# PM12_ADT7311.net
KiCad netlist of a schematic drawn in Altium Designer
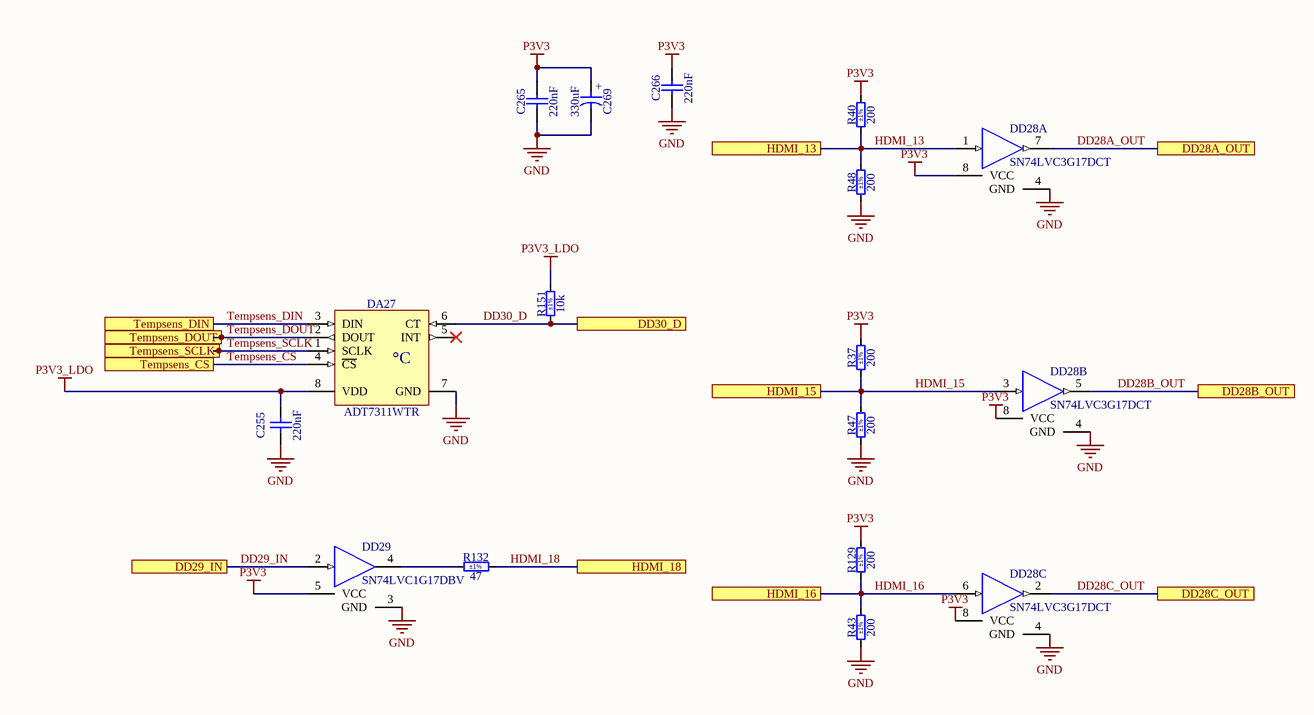
[diagram p0: PM12_ADT7311.SchDoc]

(export (version "E")
  (design (tool "Eeschema 10.0.6"))
  (components
    (comp (ref "C255")
      (value "220nF")
      (footprint "CAPC2012X135N")
      (description "Non-polarised capacitor")
      (fields
        (field (name "PART NUMBER") "CC0805_220NF_50V_10%_X7R")
        (field (name "VOLTAGE") "50V")
        (field (name "AUTHOR") "CERN DEM JLC")
      )
      (libsource (lib "Capacitors") (part "Capacitor - non polarized"))
    )
    (comp (ref "C265")
      (value "220nF")
      (footprint "CAPC2012X135N")
      (description "Non-polarised capacitor")
      (fields
        (field (name "PART NUMBER") "CC0805_220NF_50V_10%_X7R")
        (field (name "VOLTAGE") "50V")
        (field (name "AUTHOR") "CERN DEM JLC")
      )
      (libsource (lib "Capacitors") (part "Capacitor - non polarized"))
    )
    (comp (ref "C266")
      (value "220nF")
      (footprint "CAPC2012X135N")
      (description "Non-polarised capacitor")
      (fields
        (field (name "PART NUMBER") "CC0805_220NF_50V_10%_X7R")
        (field (name "VOLTAGE") "50V")
        (field (name "AUTHOR") "CERN DEM JLC")
      )
      (libsource (lib "Capacitors") (part "Capacitor - non polarized"))
    )
    (comp (ref "C269")
      (value "330uF")
      (footprint "CAPMP7343X310N")
      (description "Polarised capacitor")
      (fields
        (field (name "PART NUMBER") "CTE7343-31_330UF_6.3V_20%_LESR0015_KEMET_T520")
        (field (name "VOLTAGE") "6.3V")
        (field (name "AUTHOR") "CERN DEM JLC")
      )
      (libsource (lib "Capacitors") (part "Capacitor - polarized"))
    )
    (comp (ref "DA27")
      (value "ADT7311WTR")
      (footprint "SOIC127P600X175-8N")
      (description "±0.5°C Accurate, 16-Bit Digital SPI Temperature Sensor")
      (fields (field (name "MANUFACTURER") "ANALOG DEVICES") (field (name "AUTHOR") "CERN DEM HF"))
      (libsource (lib "ICs And Semiconductors") (part "ADT7311WTR"))
    )
    (comp (ref "DD28")
      (value "SN74LVC3G17DCT")
      (footprint "SOP65P400X130-8N")
      (description "Triple Schmitt-Trigger Buffer")
      (fields (field (name "MANUFACTURER") "TEXAS INSTRUMENTS") (field (name "AUTHOR") "CERN DEM HF"))
      (libsource (lib "ICs And Semiconductors") (part "743G17"))
    )
    (comp (ref "DD29")
      (value "SN74LVC1G17DBV")
      (footprint "SOT95P280X145-5N")
      (description "Single Schmitt-Trigger Buffer")
      (fields
        (field (name "PART NUMBER") "SN74LVC1G17DBVR")
        (field (name "MANUFACTURER") "TEXAS INSTRUMENTS")
        (field (name "AUTHOR") "CERN DEM JLC")
      )
      (libsource (lib "ICs And Semiconductors") (part "741G17"))
    )
    (comp (ref "R37")
      (value "200")
      (footprint "RESC2012X60N")
      (description "Resistor - 1%")
      (fields
        (field (name "TOLERANCE") "±1%")
        (field (name "PART NUMBER") "R0805_200R_1%_0.125W_100PPM")
        (field (name "POWER") "0.125W")
        (field (name "AUTHOR") "CERN DEM JLC")
      )
      (libsource (lib "Resistors") (part "Resistor - 1%"))
    )
    (comp (ref "R40")
      (value "200")
      (footprint "RESC2012X60N")
      (description "Resistor - 1%")
      (fields
        (field (name "TOLERANCE") "±1%")
        (field (name "PART NUMBER") "R0805_200R_1%_0.125W_100PPM")
        (field (name "POWER") "0.125W")
        (field (name "AUTHOR") "CERN DEM JLC")
      )
      (libsource (lib "Resistors") (part "Resistor - 1%"))
    )
    (comp (ref "R43")
      (value "200")
      (footprint "RESC2012X60N")
      (description "Resistor - 1%")
      (fields
        (field (name "TOLERANCE") "±1%")
        (field (name "PART NUMBER") "R0805_200R_1%_0.125W_100PPM")
        (field (name "POWER") "0.125W")
        (field (name "AUTHOR") "CERN DEM JLC")
      )
      (libsource (lib "Resistors") (part "Resistor - 1%"))
    )
    (comp (ref "R47")
      (value "200")
      (footprint "RESC2012X60N")
      (description "Resistor - 1%")
      (fields
        (field (name "TOLERANCE") "±1%")
        (field (name "PART NUMBER") "R0805_200R_1%_0.125W_100PPM")
        (field (name "POWER") "0.125W")
        (field (name "AUTHOR") "CERN DEM JLC")
      )
      (libsource (lib "Resistors") (part "Resistor - 1%"))
    )
    (comp (ref "R48")
      (value "200")
      (footprint "RESC2012X60N")
      (description "Resistor - 1%")
      (fields
        (field (name "TOLERANCE") "±1%")
        (field (name "PART NUMBER") "R0805_200R_1%_0.125W_100PPM")
        (field (name "POWER") "0.125W")
        (field (name "AUTHOR") "CERN DEM JLC")
      )
      (libsource (lib "Resistors") (part "Resistor - 1%"))
    )
    (comp (ref "R129")
      (value "200")
      (footprint "RESC2012X60N")
      (description "Resistor - 1%")
      (fields
        (field (name "TOLERANCE") "±1%")
        (field (name "PART NUMBER") "R0805_200R_1%_0.125W_100PPM")
        (field (name "POWER") "0.125W")
        (field (name "AUTHOR") "CERN DEM JLC")
      )
      (libsource (lib "Resistors") (part "Resistor - 1%"))
    )
    (comp (ref "R132")
      (value "47")
      (footprint "RESC2012X60N")
      (description "Resistor - 1%")
      (fields
        (field (name "TOLERANCE") "±1%")
        (field (name "PART NUMBER") "R0805_47R_1%_0.125W_100PPM")
        (field (name "POWER") "0.125W")
        (field (name "AUTHOR") "CERN DEM JLC")
      )
      (libsource (lib "Resistors") (part "Resistor - 1%"))
    )
    (comp (ref "R151")
      (value "10k")
      (footprint "RESC2012X60N")
      (description "Resistor - 1%")
      (fields
        (field (name "TOLERANCE") "±1%")
        (field (name "PART NUMBER") "R0805_10K_1%_0.125W_100PPM")
        (field (name "POWER") "0.125W")
        (field (name "AUTHOR") "CERN DEM JLC")
      )
      (libsource (lib "Resistors") (part "Resistor - 1%"))
    )
  )
  (nets
    (net (code "1") (name "/DD28A_OUT") (class "Default")
      (node (ref "DD28") (pin "7") (pinfunction "OUT_7") (pintype "output"))
    )
    (net (code "2") (name "/DD28B_OUT") (class "Default")
      (node (ref "DD28") (pin "5") (pinfunction "OUT_5") (pintype "output"))
    )
    (net (code "3") (name "/DD28C_OUT") (class "Default")
      (node (ref "DD28") (pin "2") (pinfunction "OUT_2") (pintype "output"))
    )
    (net (code "4") (name "/DD29_IN") (class "Default")
      (node (ref "DD29") (pin "2") (pinfunction "IN_2") (pintype "input"))
    )
    (net (code "5") (name "/DD30_D") (class "Default")
      (node (ref "DA27") (pin "6") (pinfunction "CT_6") (pintype "input"))
      (node (ref "R151") (pin "1") (pinfunction "1_1") (pintype "passive"))
    )
    (net (code "6") (name "/HDMI_13") (class "Default")
      (node (ref "DD28") (pin "1") (pinfunction "IN_1") (pintype "input"))
      (node (ref "R40") (pin "1") (pinfunction "1_1") (pintype "passive"))
      (node (ref "R48") (pin "2") (pinfunction "2_2") (pintype "passive"))
    )
    (net (code "7") (name "/HDMI_15") (class "Default")
      (node (ref "DD28") (pin "3") (pinfunction "IN_3") (pintype "input"))
      (node (ref "R37") (pin "1") (pinfunction "1_1") (pintype "passive"))
      (node (ref "R47") (pin "2") (pinfunction "2_2") (pintype "passive"))
    )
    (net (code "8") (name "/HDMI_16") (class "Default")
      (node (ref "DD28") (pin "6") (pinfunction "IN_6") (pintype "input"))
      (node (ref "R129") (pin "1") (pinfunction "1_1") (pintype "passive"))
      (node (ref "R43") (pin "2") (pinfunction "2_2") (pintype "passive"))
    )
    (net (code "9") (name "/HDMI_18") (class "Default")
      (node (ref "R132") (pin "2") (pinfunction "2_2") (pintype "passive"))
    )
    (net (code "10") (name "/Tempsens_CS") (class "Default")
      (node (ref "DA27") (pin "4") (pinfunction "~{CS}_4") (pintype "input"))
    )
    (net (code "11") (name "/Tempsens_DIN") (class "Default")
      (node (ref "DA27") (pin "3") (pinfunction "DIN_3") (pintype "input"))
    )
    (net (code "12") (name "/Tempsens_DOUT") (class "Default")
      (node (ref "DA27") (pin "2") (pinfunction "DOUT_2") (pintype "output"))
    )
    (net (code "13") (name "/Tempsens_SCLK") (class "Default")
      (node (ref "DA27") (pin "1") (pinfunction "SCLK_1") (pintype "input"))
    )
    (net (code "14") (name "GND") (class "Default")
      (node (ref "C255") (pin "1") (pinfunction "1_1") (pintype "passive"))
      (node (ref "C265") (pin "1") (pinfunction "1_1") (pintype "passive"))
      (node (ref "C266") (pin "1") (pinfunction "1_1") (pintype "passive"))
      (node (ref "C269") (pin "2") (pinfunction "2_2") (pintype "passive"))
      (node (ref "DA27") (pin "7") (pinfunction "GND_7") (pintype "power_in"))
      (node (ref "DD28") (pin "4") (pinfunction "GND_4") (pintype "power_in"))
      (node (ref "DD29") (pin "3") (pinfunction "GND_3") (pintype "power_in"))
      (node (ref "R43") (pin "1") (pinfunction "1_1") (pintype "passive"))
      (node (ref "R47") (pin "1") (pinfunction "1_1") (pintype "passive"))
      (node (ref "R48") (pin "1") (pinfunction "1_1") (pintype "passive"))
    )
    (net (code "15") (name "Net-(DD29-OUT)") (class "Default")
      (node (ref "DD29") (pin "4") (pinfunction "OUT_4") (pintype "open_collector"))
      (node (ref "R132") (pin "1") (pinfunction "1_1") (pintype "passive"))
    )
    (net (code "16") (name "P3V3") (class "Default")
      (node (ref "C265") (pin "2") (pinfunction "2_2") (pintype "passive"))
      (node (ref "C266") (pin "2") (pinfunction "2_2") (pintype "passive"))
      (node (ref "C269") (pin "1") (pinfunction "1_1") (pintype "passive"))
      (node (ref "DD28") (pin "8") (pinfunction "VCC_8") (pintype "power_in"))
      (node (ref "DD29") (pin "5") (pinfunction "VCC_5") (pintype "power_in"))
      (node (ref "R129") (pin "2") (pinfunction "2_2") (pintype "passive"))
      (node (ref "R37") (pin "2") (pinfunction "2_2") (pintype "passive"))
      (node (ref "R40") (pin "2") (pinfunction "2_2") (pintype "passive"))
    )
    (net (code "17") (name "P3V3_LDO") (class "Default")
      (node (ref "C255") (pin "2") (pinfunction "2_2") (pintype "passive"))
      (node (ref "DA27") (pin "8") (pinfunction "VDD_8") (pintype "power_in"))
      (node (ref "R151") (pin "2") (pinfunction "2_2") (pintype "passive"))
    )
    (net (code "18") (name "unconnected-(DA27-INT-Pad5)") (class "Default")
      (node (ref "DA27") (pin "5") (pinfunction "INT_5") (pintype "output+no_connect"))
    )
  )
)
